# SpindlePID.net
KiCad netlist of a schematic drawn in EAGLE
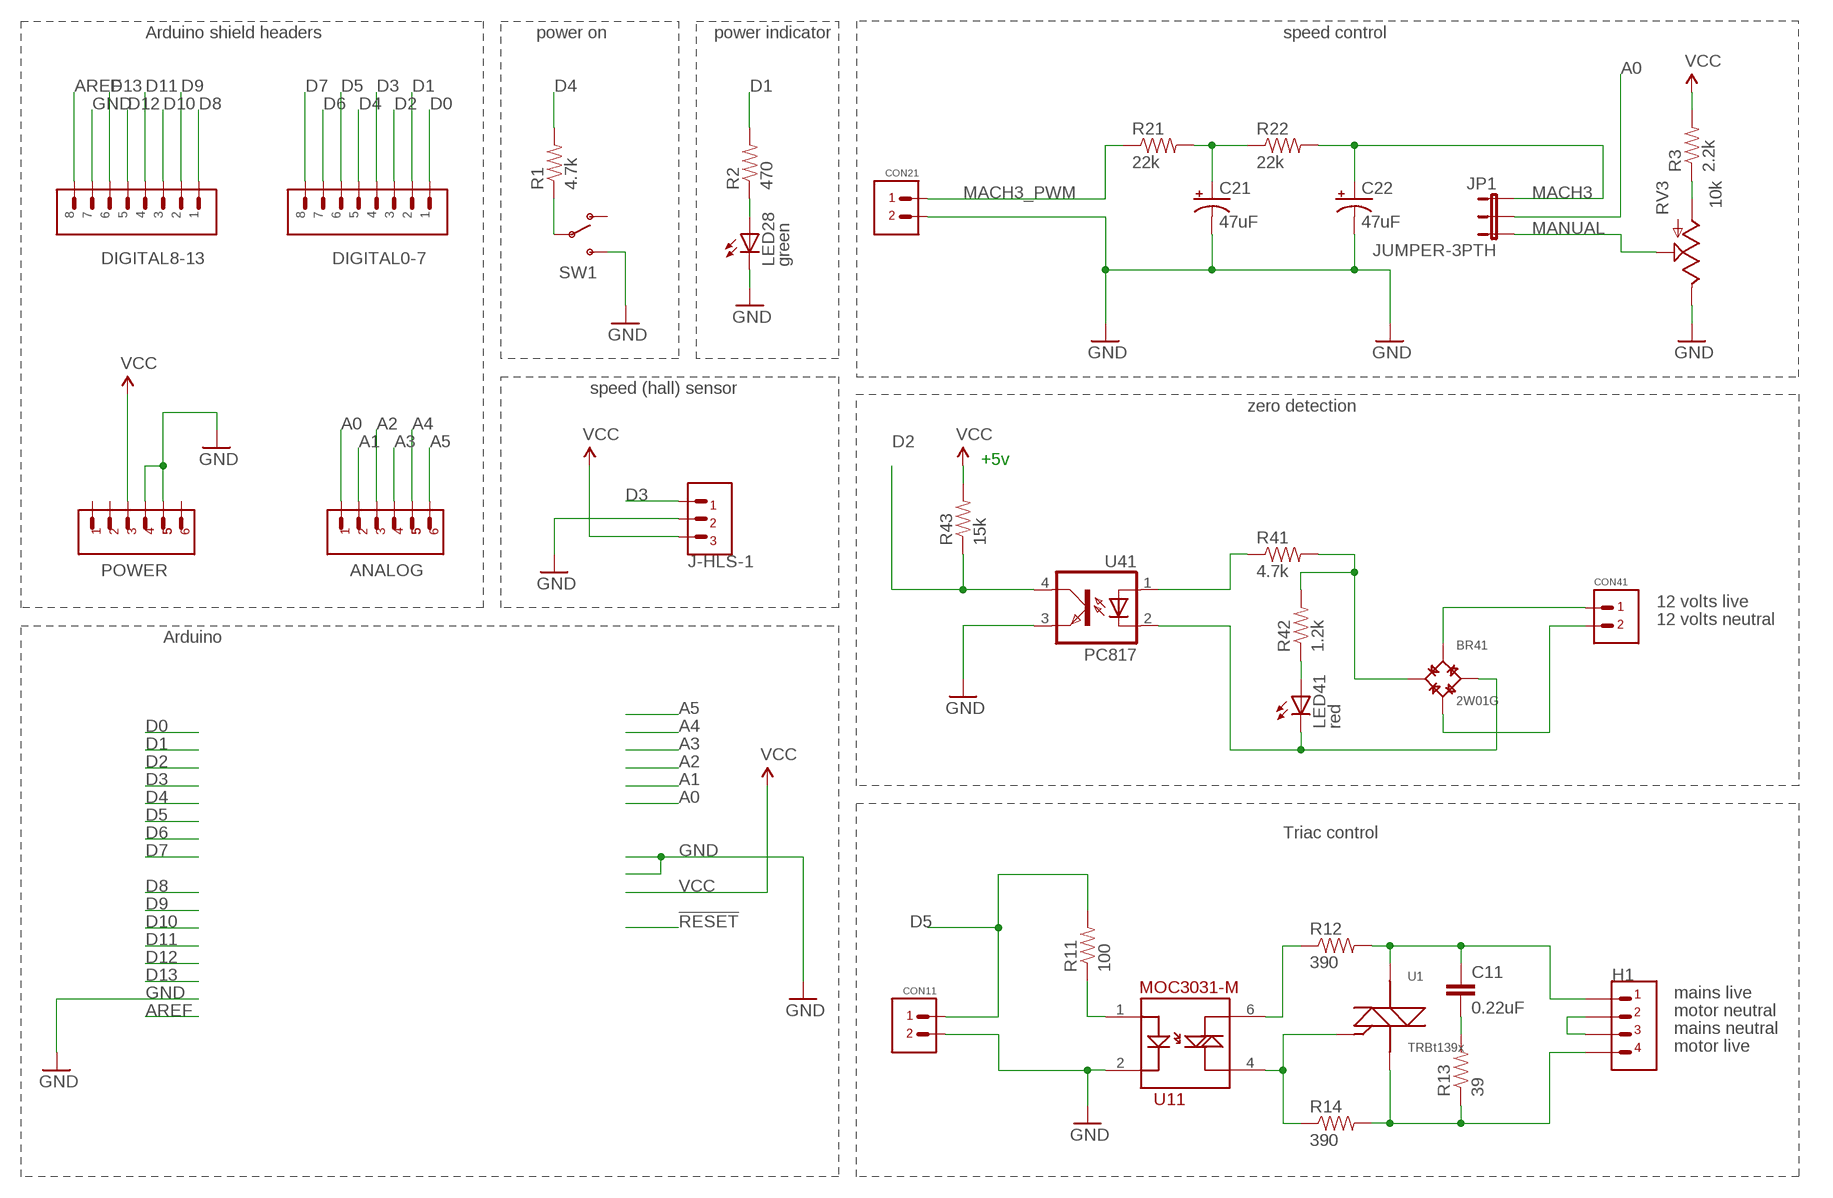
[diagram p0: schematic, sheet 1]

(export (version "E")
  (design (tool "Eeschema 10.0.6"))
  (components
    (comp (ref "ANALOG")
      (value "6PINHEADER0.1\"")
      (footprint "eagle-import:6PINHEADER")
      (libsource (lib "eagle-import") (part "6PINHEADER0.1{dblquote}"))
    )
    (comp (ref "BR41")
      (value "2W01G")
      (footprint "eagle-import:DIODEBRIDGE")
      (libsource (lib "eagle-import") (part "DIODEBRIDGE"))
    )
    (comp (ref "C11")
      (value "0.22uF")
      (footprint "eagle-import:CAP-PTH-SMALL")
      (libsource (lib "eagle-import") (part "CAPPTH"))
    )
    (comp (ref "C21")
      (value "47uF")
      (footprint "eagle-import:CPOL-RADIAL-10UF-25V")
      (libsource (lib "eagle-import") (part "CAP_POLPTH2"))
    )
    (comp (ref "C22")
      (value "47uF")
      (footprint "eagle-import:CPOL-RADIAL-10UF-25V")
      (libsource (lib "eagle-import") (part "CAP_POLPTH2"))
    )
    (comp (ref "CON11")
      (value "2PINHEADER")
      (footprint "eagle-import:2PINHEADER")
      (libsource (lib "eagle-import") (part "2PINHEADER"))
    )
    (comp (ref "CON21")
      (value "2PINHEADER")
      (footprint "eagle-import:2PINHEADER")
      (libsource (lib "eagle-import") (part "2PINHEADER"))
    )
    (comp (ref "CON41")
      (value "2PINHEADER")
      (footprint "eagle-import:2PINHEADER")
      (libsource (lib "eagle-import") (part "2PINHEADER"))
    )
    (comp (ref "DIGITAL0-7")
      (value "8PINHEADER")
      (footprint "eagle-import:8PINHEADER")
      (libsource (lib "eagle-import") (part "8PINHEADER"))
    )
    (comp (ref "DIGITAL8-13")
      (value "8PINHEADER")
      (footprint "eagle-import:8PINHEADER")
      (libsource (lib "eagle-import") (part "8PINHEADER"))
    )
    (comp (ref "H1")
      (value "4PIN")
      (footprint "eagle-import:4PIN")
      (libsource (lib "eagle-import") (part "4PIN"))
    )
    (comp (ref "J-HLS-1")
      (value "3PINHEADER")
      (footprint "eagle-import:3PINHEADER")
      (libsource (lib "eagle-import") (part "3PINHEADER"))
    )
    (comp (ref "JP1")
      (value "JUMPER-3PTH")
      (footprint "eagle-import:1X03")
      (libsource (lib "eagle-import") (part "JUMPER-3PTH"))
    )
    (comp (ref "LED28")
      (value "green")
      (footprint "eagle-import:LED5MM")
      (libsource (lib "eagle-import") (part "LED5MM"))
    )
    (comp (ref "LED41")
      (value "red")
      (footprint "eagle-import:LED5MM")
      (libsource (lib "eagle-import") (part "LED5MM"))
    )
    (comp (ref "POWER")
      (value "6PINHEADER0.1\"")
      (footprint "eagle-import:6PINHEADER")
      (libsource (lib "eagle-import") (part "6PINHEADER0.1{dblquote}"))
    )
    (comp (ref "R1")
      (value "4.7k")
      (footprint "eagle-import:1_6W-RES")
      (libsource (lib "eagle-import") (part "RESISTORPTH-1/6W"))
    )
    (comp (ref "R2")
      (value "470")
      (footprint "eagle-import:1_6W-RES")
      (libsource (lib "eagle-import") (part "RESISTORPTH-1/6W"))
    )
    (comp (ref "R3")
      (value "2.2k")
      (footprint "eagle-import:1_6W-RES")
      (libsource (lib "eagle-import") (part "RESISTORPTH-1/6W"))
    )
    (comp (ref "R11")
      (value "100")
      (footprint "eagle-import:1_6W-RES")
      (libsource (lib "eagle-import") (part "RESISTORPTH-1/6W"))
    )
    (comp (ref "R12")
      (value "390")
      (footprint "eagle-import:1_6W-RES")
      (libsource (lib "eagle-import") (part "RESISTORPTH-1/6W"))
    )
    (comp (ref "R13")
      (value "39")
      (footprint "eagle-import:1_6W-RES")
      (libsource (lib "eagle-import") (part "RESISTORPTH-1/6W"))
    )
    (comp (ref "R14")
      (value "390")
      (footprint "eagle-import:1_6W-RES")
      (libsource (lib "eagle-import") (part "RESISTORPTH-1/6W"))
    )
    (comp (ref "R21")
      (value "22k")
      (footprint "eagle-import:1_6W-RES")
      (libsource (lib "eagle-import") (part "RESISTORPTH-1/6W"))
    )
    (comp (ref "R22")
      (value "22k")
      (footprint "eagle-import:1_6W-RES")
      (libsource (lib "eagle-import") (part "RESISTORPTH-1/6W"))
    )
    (comp (ref "R41")
      (value "4.7k")
      (footprint "eagle-import:1_6W-RES")
      (libsource (lib "eagle-import") (part "RESISTORPTH-1/6W"))
    )
    (comp (ref "R42")
      (value "1.2k")
      (footprint "eagle-import:1_6W-RES")
      (libsource (lib "eagle-import") (part "RESISTORPTH-1/6W"))
    )
    (comp (ref "R43")
      (value "15k")
      (footprint "eagle-import:1_6W-RES")
      (libsource (lib "eagle-import") (part "RESISTORPTH-1/6W"))
    )
    (comp (ref "RV3")
      (value "10k")
      (footprint "eagle-import:TRIM_POT")
      (libsource (lib "eagle-import") (part "POTTRIM"))
    )
    (comp (ref "SW1")
      (value "SWITCH-SPSTPTH")
      (footprint "eagle-import:SWITCH-SPDT")
      (libsource (lib "eagle-import") (part "SWITCH-SPSTPTH"))
    )
    (comp (ref "U1")
      (value "TRBt139x")
      (footprint "eagle-import:TRIAC")
      (libsource (lib "eagle-import") (part "TRIAC"))
    )
    (comp (ref "U11")
      (value "MOC3031-M")
      (footprint "eagle-import:DIL06")
      (libsource (lib "eagle-import") (part "MOC3031-M"))
    )
    (comp (ref "U41")
      (value "PC817")
      (footprint "eagle-import:DIL04")
      (fields (field (name "MPN") "PC817X4J000F"))
      (libsource (lib "eagle-import") (part "PC817"))
    )
  )
  (nets
    (net (code "1") (name "/A0") (class "Default")
      (node (ref "ANALOG") (pin "P$1") (pinfunction "P$1_P$1") (pintype "bidirectional"))
      (node (ref "JP1") (pin "2") (pinfunction "2_2") (pintype "passive"))
    )
    (net (code "2") (name "/A1") (class "Default")
      (node (ref "ANALOG") (pin "P$2") (pinfunction "P$2_P$2") (pintype "bidirectional"))
    )
    (net (code "3") (name "/A2") (class "Default")
      (node (ref "ANALOG") (pin "P$3") (pinfunction "P$3_P$3") (pintype "bidirectional"))
    )
    (net (code "4") (name "/A3") (class "Default")
      (node (ref "ANALOG") (pin "P$4") (pinfunction "P$4_P$4") (pintype "bidirectional"))
    )
    (net (code "5") (name "/A4") (class "Default")
      (node (ref "ANALOG") (pin "P$5") (pinfunction "P$5_P$5") (pintype "bidirectional"))
    )
    (net (code "6") (name "/A5") (class "Default")
      (node (ref "ANALOG") (pin "P$6") (pinfunction "P$6_P$6") (pintype "bidirectional"))
    )
    (net (code "7") (name "/AREF") (class "Default")
      (node (ref "DIGITAL8-13") (pin "P$8") (pinfunction "P$8_P$8") (pintype "bidirectional"))
    )
    (net (code "8") (name "/D0") (class "Default")
      (node (ref "DIGITAL0-7") (pin "P$1") (pinfunction "P$1_P$1") (pintype "bidirectional"))
    )
    (net (code "9") (name "/D1") (class "Default")
      (node (ref "DIGITAL0-7") (pin "P$2") (pinfunction "P$2_P$2") (pintype "bidirectional"))
      (node (ref "R2") (pin "2") (pinfunction "2_2") (pintype "passive"))
    )
    (net (code "10") (name "/D2") (class "Default")
      (node (ref "DIGITAL0-7") (pin "P$3") (pinfunction "P$3_P$3") (pintype "bidirectional"))
      (node (ref "R43") (pin "1") (pinfunction "1_1") (pintype "passive"))
      (node (ref "U41") (pin "4") (pinfunction "COL_4") (pintype "passive"))
    )
    (net (code "11") (name "/D3") (class "Default")
      (node (ref "DIGITAL0-7") (pin "P$4") (pinfunction "P$4_P$4") (pintype "bidirectional"))
      (node (ref "J-HLS-1") (pin "P$3") (pinfunction "P$3_P$3") (pintype "bidirectional"))
    )
    (net (code "12") (name "/D4") (class "Default")
      (node (ref "DIGITAL0-7") (pin "P$5") (pinfunction "P$5_P$5") (pintype "bidirectional"))
      (node (ref "R1") (pin "2") (pinfunction "2_2") (pintype "passive"))
    )
    (net (code "13") (name "/D5") (class "Default")
      (node (ref "CON11") (pin "P$1") (pinfunction "P$1_P$1") (pintype "bidirectional"))
      (node (ref "DIGITAL0-7") (pin "P$6") (pinfunction "P$6_P$6") (pintype "bidirectional"))
      (node (ref "R11") (pin "2") (pinfunction "2_2") (pintype "passive"))
    )
    (net (code "14") (name "/D6") (class "Default")
      (node (ref "DIGITAL0-7") (pin "P$7") (pinfunction "P$7_P$7") (pintype "bidirectional"))
    )
    (net (code "15") (name "/D7") (class "Default")
      (node (ref "DIGITAL0-7") (pin "P$8") (pinfunction "P$8_P$8") (pintype "bidirectional"))
    )
    (net (code "16") (name "/D8") (class "Default")
      (node (ref "DIGITAL8-13") (pin "P$1") (pinfunction "P$1_P$1") (pintype "bidirectional"))
    )
    (net (code "17") (name "/D9") (class "Default")
      (node (ref "DIGITAL8-13") (pin "P$2") (pinfunction "P$2_P$2") (pintype "bidirectional"))
    )
    (net (code "18") (name "/D10") (class "Default")
      (node (ref "DIGITAL8-13") (pin "P$3") (pinfunction "P$3_P$3") (pintype "bidirectional"))
    )
    (net (code "19") (name "/D11") (class "Default")
      (node (ref "DIGITAL8-13") (pin "P$4") (pinfunction "P$4_P$4") (pintype "bidirectional"))
    )
    (net (code "20") (name "/D12") (class "Default")
      (node (ref "DIGITAL8-13") (pin "P$5") (pinfunction "P$5_P$5") (pintype "bidirectional"))
    )
    (net (code "21") (name "/D13") (class "Default")
      (node (ref "DIGITAL8-13") (pin "P$6") (pinfunction "P$6_P$6") (pintype "bidirectional"))
    )
    (net (code "22") (name "/MACH3") (class "Default")
      (node (ref "C22") (pin "1") (pinfunction "+_1") (pintype "passive"))
      (node (ref "JP1") (pin "1") (pinfunction "1_1") (pintype "passive"))
      (node (ref "R22") (pin "2") (pinfunction "2_2") (pintype "passive"))
    )
    (net (code "23") (name "/MACH3_PWM") (class "Default")
      (node (ref "CON21") (pin "P$1") (pinfunction "P$1_P$1") (pintype "bidirectional"))
      (node (ref "R21") (pin "1") (pinfunction "1_1") (pintype "passive"))
    )
    (net (code "24") (name "/MANUAL") (class "Default")
      (node (ref "JP1") (pin "3") (pinfunction "3_3") (pintype "passive"))
      (node (ref "RV3") (pin "1") (pinfunction "S_1") (pintype "passive"))
    )
    (net (code "26") (name "GND") (class "Default")
      (node (ref "C21") (pin "2") (pinfunction "-_2") (pintype "passive"))
      (node (ref "C22") (pin "2") (pinfunction "-_2") (pintype "passive"))
      (node (ref "CON11") (pin "P$2") (pinfunction "P$2_P$2") (pintype "bidirectional"))
      (node (ref "CON21") (pin "P$2") (pinfunction "P$2_P$2") (pintype "bidirectional"))
      (node (ref "DIGITAL8-13") (pin "P$7") (pinfunction "P$7_P$7") (pintype "bidirectional"))
      (node (ref "J-HLS-1") (pin "P$2") (pinfunction "P$2_P$2") (pintype "bidirectional"))
      (node (ref "LED28") (pin "K") (pinfunction "C_K") (pintype "passive"))
      (node (ref "POWER") (pin "P$4") (pinfunction "P$4_P$4") (pintype "bidirectional"))
      (node (ref "POWER") (pin "P$5") (pinfunction "P$5_P$5") (pintype "bidirectional"))
      (node (ref "RV3") (pin "2") (pinfunction "E_2") (pintype "passive"))
      (node (ref "SW1") (pin "3") (pinfunction "S_3") (pintype "passive"))
      (node (ref "U11") (pin "2") (pinfunction "2_2") (pintype "bidirectional"))
      (node (ref "U41") (pin "3") (pinfunction "EMIT_3") (pintype "passive"))
    )
    (net (code "27") (name "Net-(BR41-Pad+)") (class "Default")
      (node (ref "BR41") (pin "+") (pinfunction "+_+") (pintype "bidirectional"))
      (node (ref "R41") (pin "2") (pinfunction "2_2") (pintype "passive"))
      (node (ref "R42") (pin "2") (pinfunction "2_2") (pintype "passive"))
    )
    (net (code "28") (name "Net-(BR41-PadAC1)") (class "Default")
      (node (ref "BR41") (pin "AC1") (pinfunction "AC1_AC1") (pintype "bidirectional"))
      (node (ref "CON41") (pin "P$1") (pinfunction "P$1_P$1") (pintype "bidirectional"))
    )
    (net (code "29") (name "Net-(BR41-PadAC2)") (class "Default")
      (node (ref "BR41") (pin "AC2") (pinfunction "AC2_AC2") (pintype "bidirectional"))
      (node (ref "CON41") (pin "P$2") (pinfunction "P$2_P$2") (pintype "bidirectional"))
    )
    (net (code "30") (name "Net-(C11-Pad2)") (class "Default")
      (node (ref "C11") (pin "2") (pinfunction "2_2") (pintype "passive"))
      (node (ref "R13") (pin "2") (pinfunction "2_2") (pintype "passive"))
    )
    (net (code "31") (name "Net-(C21-+)") (class "Default")
      (node (ref "C21") (pin "1") (pinfunction "+_1") (pintype "passive"))
      (node (ref "R21") (pin "2") (pinfunction "2_2") (pintype "passive"))
      (node (ref "R22") (pin "1") (pinfunction "1_1") (pintype "passive"))
    )
    (net (code "32") (name "Net-(H1-PadP$2)") (class "Default")
      (node (ref "H1") (pin "P$2") (pinfunction "P$2_P$2") (pintype "bidirectional"))
      (node (ref "H1") (pin "P$3") (pinfunction "P$3_P$3") (pintype "bidirectional"))
    )
    (net (code "33") (name "Net-(LED28-PadA)") (class "Default")
      (node (ref "LED28") (pin "A") (pinfunction "A_A") (pintype "passive"))
      (node (ref "R2") (pin "1") (pinfunction "1_1") (pintype "passive"))
    )
    (net (code "34") (name "Net-(LED41-C)") (class "Default")
      (node (ref "BR41") (pin "-") (pinfunction "-_-") (pintype "bidirectional"))
      (node (ref "LED41") (pin "K") (pinfunction "C_K") (pintype "passive"))
      (node (ref "U41") (pin "2") (pinfunction "C_2") (pintype "passive"))
    )
    (net (code "35") (name "Net-(LED41-PadA)") (class "Default")
      (node (ref "LED41") (pin "A") (pinfunction "A_A") (pintype "passive"))
      (node (ref "R42") (pin "1") (pinfunction "1_1") (pintype "passive"))
    )
    (net (code "36") (name "Net-(R11-Pad1)") (class "Default")
      (node (ref "R11") (pin "1") (pinfunction "1_1") (pintype "passive"))
      (node (ref "U11") (pin "1") (pinfunction "1_1") (pintype "bidirectional"))
    )
    (net (code "37") (name "Net-(R12-Pad1)") (class "Default")
      (node (ref "R12") (pin "1") (pinfunction "1_1") (pintype "passive"))
      (node (ref "U11") (pin "6") (pinfunction "6_6") (pintype "bidirectional"))
    )
    (net (code "38") (name "Net-(RV3-A)") (class "Default")
      (node (ref "R3") (pin "1") (pinfunction "1_1") (pintype "passive"))
      (node (ref "RV3") (pin "3") (pinfunction "A_3") (pintype "passive"))
    )
    (net (code "39") (name "Net-(SW1-P)") (class "Default")
      (node (ref "R1") (pin "1") (pinfunction "1_1") (pintype "passive"))
      (node (ref "SW1") (pin "2") (pinfunction "P_2") (pintype "passive"))
    )
    (net (code "40") (name "Net-(U1-A)") (class "Default")
      (node (ref "C11") (pin "1") (pinfunction "1_1") (pintype "passive"))
      (node (ref "H1") (pin "P$1") (pinfunction "P$1_P$1") (pintype "bidirectional"))
      (node (ref "R12") (pin "2") (pinfunction "2_2") (pintype "passive"))
      (node (ref "U1") (pin "2") (pinfunction "A_2") (pintype "bidirectional"))
    )
    (net (code "41") (name "Net-(U1-B)") (class "Default")
      (node (ref "R14") (pin "1") (pinfunction "1_1") (pintype "passive"))
      (node (ref "U1") (pin "1") (pinfunction "B_1") (pintype "bidirectional"))
      (node (ref "U11") (pin "4") (pinfunction "4_4") (pintype "bidirectional"))
    )
    (net (code "42") (name "Net-(U1-C)") (class "Default")
      (node (ref "H1") (pin "P$4") (pinfunction "P$4_P$4") (pintype "bidirectional"))
      (node (ref "R13") (pin "1") (pinfunction "1_1") (pintype "passive"))
      (node (ref "R14") (pin "2") (pinfunction "2_2") (pintype "passive"))
      (node (ref "U1") (pin "3") (pinfunction "C_3") (pintype "bidirectional"))
    )
    (net (code "43") (name "Net-(U41-A)") (class "Default")
      (node (ref "R41") (pin "1") (pinfunction "1_1") (pintype "passive"))
      (node (ref "U41") (pin "1") (pinfunction "A_1") (pintype "passive"))
    )
    (net (code "44") (name "VCC") (class "Default")
      (node (ref "J-HLS-1") (pin "P$1") (pinfunction "P$1_P$1") (pintype "bidirectional"))
      (node (ref "POWER") (pin "P$3") (pinfunction "P$3_P$3") (pintype "bidirectional"))
      (node (ref "R3") (pin "2") (pinfunction "2_2") (pintype "passive"))
      (node (ref "R43") (pin "2") (pinfunction "2_2") (pintype "passive"))
    )
    (net (code "45") (name "unconnected-(POWER-PadP$1)") (class "Default")
      (node (ref "POWER") (pin "P$1") (pinfunction "P$1_P$1") (pintype "bidirectional"))
    )
    (net (code "46") (name "unconnected-(POWER-PadP$2)") (class "Default")
      (node (ref "POWER") (pin "P$2") (pinfunction "P$2_P$2") (pintype "bidirectional"))
    )
    (net (code "47") (name "unconnected-(POWER-PadP$6)") (class "Default")
      (node (ref "POWER") (pin "P$6") (pinfunction "P$6_P$6") (pintype "bidirectional"))
    )
    (net (code "48") (name "unconnected-(SW1-O-Pad1)") (class "Default")
      (node (ref "SW1") (pin "1") (pinfunction "O_1") (pintype "passive"))
    )
  )
)
